# Longde1.net
KiCad netlist of a schematic drawn in Altium Designer
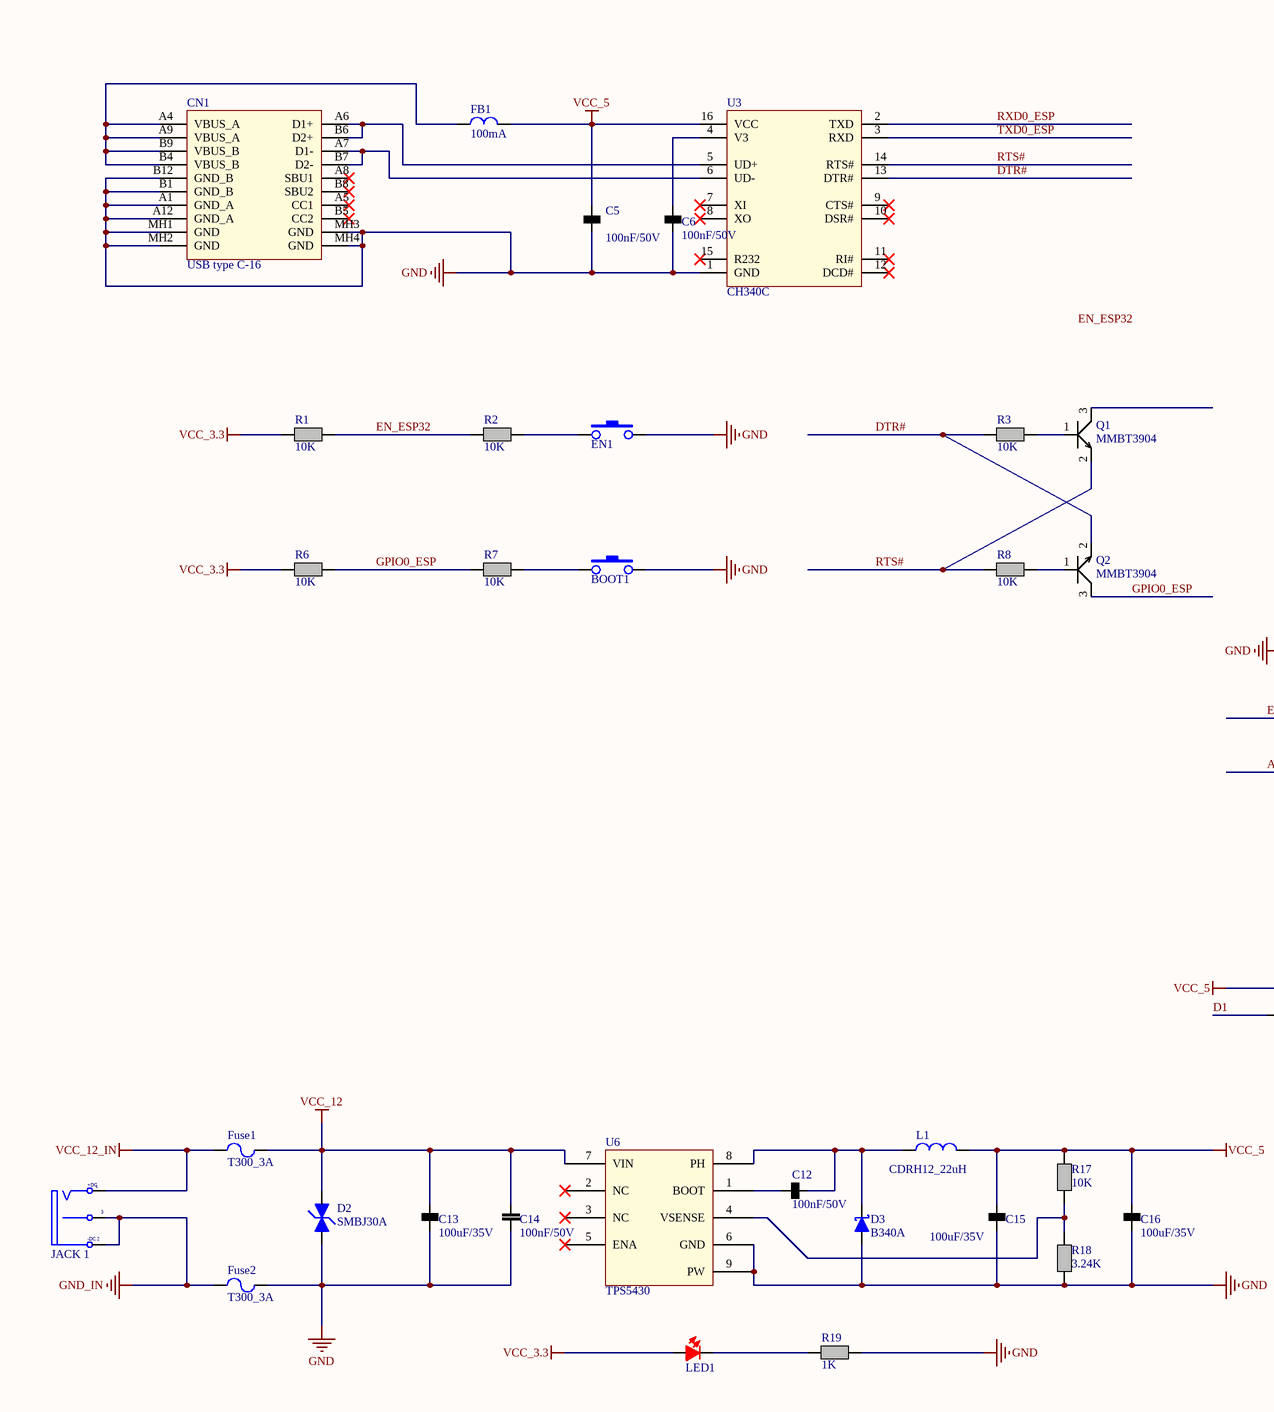
[diagram p0: Longde1.SchDoc, left]
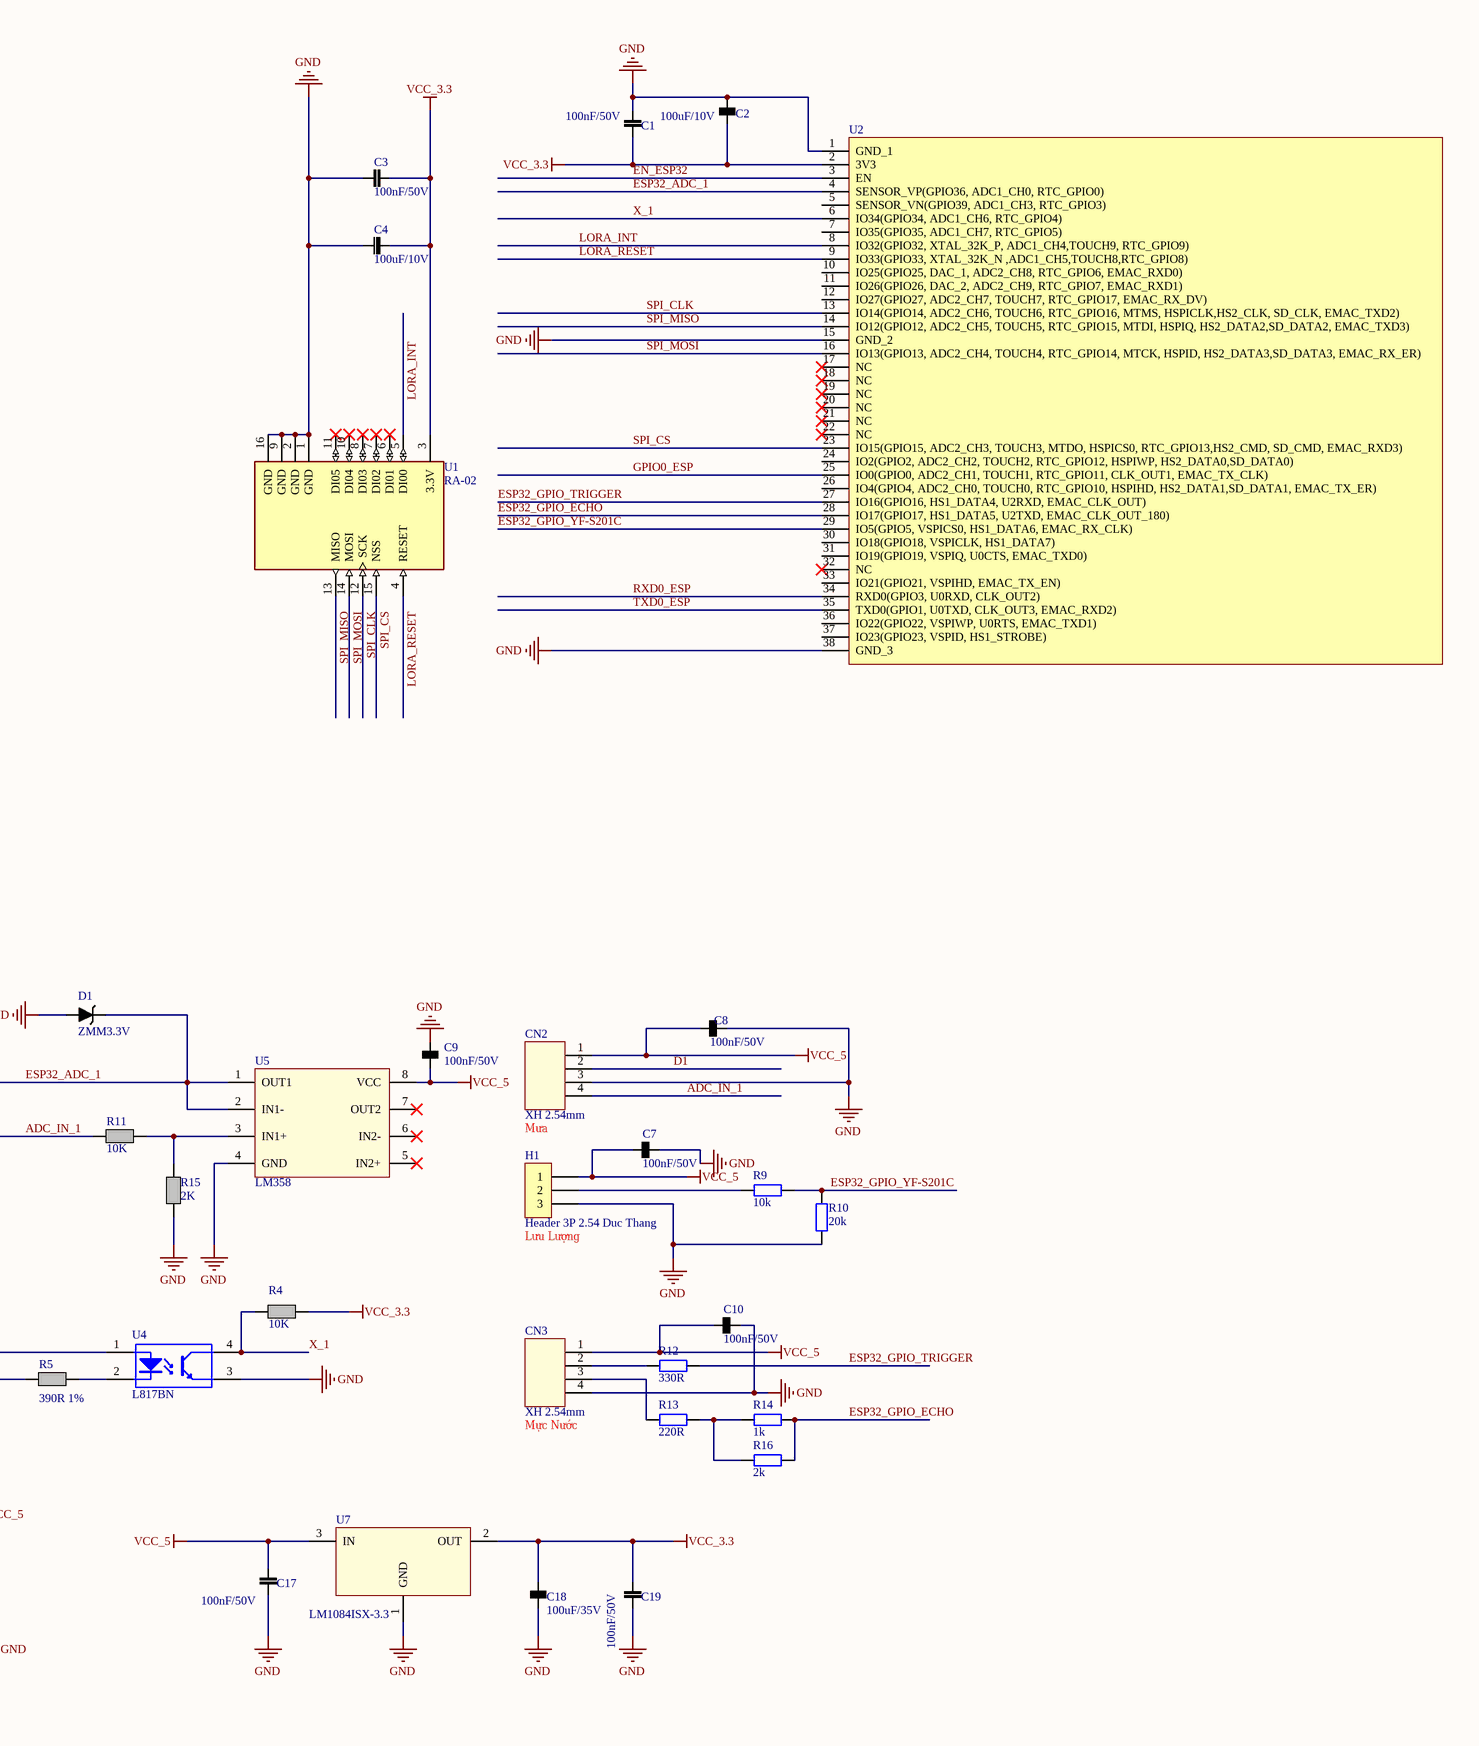
[diagram p1: Longde1.SchDoc, right]

(export (version "E")
  (design (tool "Eeschema 10.0.6"))
  (components
    (comp (ref "BOOT1")
      (value "SW_2pin_SMD")
      (footprint "SW2-SMD**")
      (libsource (lib "Milky_Way") (part "SW_2pin_SMD"))
    )
    (comp (ref "C1")
      (value "100nF/50V")
      (footprint "CAP-0805**")
      (description "2Pin-SMD-0805 ,Ceramic X7R")
      (libsource (lib "Milky_Way") (part "Cap-100nF/50V_0805"))
    )
    (comp (ref "C2")
      (value "100uF/10V")
      (footprint "CAP-TANTA-3528**")
      (description "Cap-Tantalum  SMD3528 3.5mm x 2.8mm")
      (libsource (lib "") (part "Cap-Tanta_100uF/10V 3528_1"))
    )
    (comp (ref "C3")
      (value "100nF/50V")
      (footprint "CAP-0805**")
      (description "2Pin-SMD-0805 ,Ceramic X7R")
      (libsource (lib "Milky_Way") (part "Cap-100nF/50V_0805"))
    )
    (comp (ref "C4")
      (value "100uF/10V")
      (footprint "CAP-TANTA-3528**")
      (description "Cap-Tantalum  SMD3528 3.5mm x 2.8mm")
      (libsource (lib "Milky_Way") (part "Cap-Tanta_100uF/10V 3528"))
    )
    (comp (ref "C5")
      (value "100nF/50V")
      (footprint "CAP-0805**")
      (description "2Pin-SMD-0805 ,Ceramic X7R")
      (libsource (lib "Milky_Way") (part "Cap-100nF/50V_0805"))
    )
    (comp (ref "C6")
      (value "100nF/50V")
      (footprint "CAP-0805**")
      (description "2Pin-SMD-0805 ,Ceramic X7R")
      (libsource (lib "Milky_Way") (part "Cap-100nF/50V_0805"))
    )
    (comp (ref "C7")
      (value "100nF/50V")
      (footprint "CAP-0805**")
      (description "2Pin-SMD-0805 ,Ceramic X7R")
      (libsource (lib "Milky_Way") (part "Cap-100nF/50V_0805"))
    )
    (comp (ref "C8")
      (value "100nF/50V")
      (footprint "CAP-0805**")
      (description "2Pin-SMD-0805 ,Ceramic X7R")
      (libsource (lib "Milky_Way") (part "Cap-100nF/50V_0805"))
    )
    (comp (ref "C9")
      (value "100nF/50V")
      (footprint "CAP-0805**")
      (description "2Pin-SMD-0805 ,Ceramic X7R")
      (libsource (lib "Milky_Way") (part "Cap-100nF/50V_0805"))
    )
    (comp (ref "C10")
      (value "100nF/50V")
      (footprint "CAP-0805**")
      (description "2Pin-SMD-0805 ,Ceramic X7R")
      (libsource (lib "Milky_Way") (part "Cap-100nF/50V_0805"))
    )
    (comp (ref "C12")
      (value "100nF/50V")
      (footprint "CAP-0805**")
      (description "2Pin-SMD-0805 ,Ceramic X7R")
      (libsource (lib "Milky_Way") (part "Cap-100nF/50V_0805"))
    )
    (comp (ref "C13")
      (value "100uF/35V")
      (footprint "CAP-AL- Size D8_6.3×7.7 mm**")
      (description "Cap-Al-Size D8_6.3×7.7 mm")
      (libsource (lib "Milky_Way") (part "Cap-Al_100uF/35V"))
    )
    (comp (ref "C14")
      (value "100nF/50V")
      (footprint "CAP-0805**")
      (description "2Pin-SMD-0805 ,Ceramic X7R")
      (libsource (lib "Milky_Way") (part "Cap-100nF/50V_0805"))
    )
    (comp (ref "C15")
      (value "100uF/35V")
      (footprint "CAP-AL- Size D8_6.3×7.7 mm**")
      (description "Cap-Al-Size D8_6.3×7.7 mm")
      (libsource (lib "Milky_Way") (part "Cap-Al_100uF/35V"))
    )
    (comp (ref "C16")
      (value "100uF/35V")
      (footprint "CAP-AL- Size D8_6.3×7.7 mm**")
      (description "Cap-Al-Size D8_6.3×7.7 mm")
      (libsource (lib "Milky_Way") (part "Cap-Al_100uF/35V"))
    )
    (comp (ref "C17")
      (value "100nF/50V")
      (footprint "CAP-0805**")
      (description "2Pin-SMD-0805 ,Ceramic X7R")
      (libsource (lib "Milky_Way") (part "Cap-100nF/50V_0805"))
    )
    (comp (ref "C18")
      (value "100uF/35V")
      (footprint "CAP-AL- Size D8_6.3×7.7 mm**")
      (description "Cap-Al-Size D8_6.3×7.7 mm")
      (libsource (lib "Milky_Way") (part "Cap-Al_100uF/35V"))
    )
    (comp (ref "C19")
      (value "100nF/50V")
      (footprint "CAP-0805**")
      (description "2Pin-SMD-0805 ,Ceramic X7R")
      (libsource (lib "Milky_Way") (part "Cap-100nF/50V_0805"))
    )
    (comp (ref "CN1")
      (value "USB type C-16")
      (footprint "USB TYPE C-16**")
      (fields (field (name "MF") "Valcon") (field (name "MP") "CSP-USC16-TR"))
      (libsource (lib "Milky_Way") (part "USB type C-16"))
    )
    (comp (ref "CN2")
      (value "XH 2.54mm")
      (footprint "HER_XH2.54MM _4PIN_STRAGHT**")
      (description "HER_4_XH 2.54mm")
      (libsource (lib "Milky_Way") (part "HER_4_XH 2.54mm"))
    )
    (comp (ref "CN3")
      (value "XH 2.54mm")
      (footprint "HER_XH2.54MM _4PIN_STRAGHT**")
      (description "HER_4_XH 2.54mm")
      (libsource (lib "Milky_Way") (part "HER_4_XH 2.54mm"))
    )
    (comp (ref "D1")
      (value "ZMM3.3V")
      (footprint "DIO_SOD-80C**")
      (description "DZener_ZMM3.3V,SOD-80C")
      (libsource (lib "Milky_Way") (part "DZener_ZMM3.3V"))
    )
    (comp (ref "D2")
      (value "SMBJ30A")
      (footprint "DO-214AA**")
      (description "DO-214AA**")
      (libsource (lib "Milky_Way") (part "D-TVS_SMBJ30A"))
    )
    (comp (ref "D3")
      (value "B340A")
      (footprint "DO-214AC**")
      (description "DO_214AC")
      (fields (field (name "PUBLISHER") "Altium Limited"))
      (libsource (lib "Milky_Way") (part "DSchottky_B340A"))
    )
    (comp (ref "EN1")
      (value "SW_2pin_SMD")
      (footprint "SW2-SMD**")
      (libsource (lib "Milky_Way") (part "SW_2pin_SMD"))
    )
    (comp (ref "FB1")
      (value "100mA")
      (footprint "FB 0805**")
      (description "FB0805/600R/0805")
      (fields (field (name "PUBLISHER") "Altium Limited"))
      (libsource (lib "Milky_Way") (part "FB0805/600R_0805"))
    )
    (comp (ref "Fuse1")
      (value "T300_3A")
      (footprint "FUSE-1812**")
      (description "SMD 1812")
      (libsource (lib "Milky_Way") (part "FUSE 3A _1812"))
    )
    (comp (ref "Fuse2")
      (value "T300_3A")
      (footprint "FUSE-1812**")
      (description "SMD 1812")
      (libsource (lib "Milky_Way") (part "FUSE 3A _1812"))
    )
    (comp (ref "H1")
      (value "Header 3P 2.54 Duc Thang")
      (footprint "XH2.54M-3")
      (description "Cắm")
      (libsource (lib "Altium_Lib_by_KhueNguyenCreator") (part "Header 3P 2.54 Duc Thang"))
    )
    (comp (ref "JACK 1")
      (value "DC3501")
      (footprint "DC_005**")
      (description "Jack DC3.5x1.3MM DC3501")
      (libsource (lib "Milky_Way") (part "Jack  DC3501"))
    )
    (comp (ref "L1")
      (value "CDRH12_22uH")
      (footprint "IND_CDRH12_12x12x7MM**")
      (description "CDRH12_12x12x7MM**")
      (fields
        (field (name "MANUFACTURER") "Generic Components")
        (field (name "PUBLISHER") "Altium Hobart Technology Centre")
      )
      (libsource (lib "Milky_Way") (part "IN_CDRH12_22uH"))
    )
    (comp (ref "LED1")
      (value "LedRed")
      (footprint "LED-0805-Red**")
      (description "2Pin-SMD")
      (libsource (lib "Milky_Way") (part "LedRed"))
    )
    (comp (ref "Q1")
      (value "MMBT3904")
      (footprint "SOT23-3 **")
      (description "3PIN-SOT23,MMBT3904")
      (libsource (lib "Milky_Way") (part "TRA-N_MMBT3904"))
    )
    (comp (ref "Q2")
      (value "MMBT3904")
      (footprint "SOT23-3 **")
      (description "3PIN-SOT23,MMBT3904")
      (libsource (lib "Milky_Way") (part "TRA-N_MMBT3904"))
    )
    (comp (ref "R1")
      (value "10K")
      (footprint "Res-0805**")
      (description "Res-10K 0805 SMD")
      (libsource (lib "Milky_Way") (part "Res-10K 0805 SMD"))
    )
    (comp (ref "R2")
      (value "10K")
      (footprint "Res-0805**")
      (description "Res-10K 0805 SMD")
      (libsource (lib "Milky_Way") (part "Res-10K 0805 SMD"))
    )
    (comp (ref "R3")
      (value "10K")
      (footprint "Res-0805**")
      (description "Res-10K 0805 SMD")
      (libsource (lib "Milky_Way") (part "Res-10K 0805 SMD"))
    )
    (comp (ref "R4")
      (value "10K")
      (footprint "Res-0805**")
      (description "Res-10K 0805 SMD")
      (libsource (lib "Milky_Way") (part "Res-10K 0805 SMD"))
    )
    (comp (ref "R5")
      (value "390R 1%")
      (footprint "Res-0805**")
      (libsource (lib "Milky_Way") (part "Res-390R 1% 0805 SMD"))
    )
    (comp (ref "R6")
      (value "10K")
      (footprint "Res-0805**")
      (description "Res-10K 0805 SMD")
      (libsource (lib "Milky_Way") (part "Res-10K 0805 SMD"))
    )
    (comp (ref "R7")
      (value "10K")
      (footprint "Res-0805**")
      (description "Res-10K 0805 SMD")
      (libsource (lib "Milky_Way") (part "Res-10K 0805 SMD"))
    )
    (comp (ref "R8")
      (value "10K")
      (footprint "Res-0805**")
      (description "Res-10K 0805 SMD")
      (libsource (lib "Milky_Way") (part "Res-10K 0805 SMD"))
    )
    (comp (ref "R9")
      (value "10k")
      (footprint "tro smd 0805")
      (description "Dán")
      (libsource (lib "ThuvienTHoi") (part "Tro 0805 1% 10k"))
    )
    (comp (ref "R10")
      (value "20k")
      (footprint "tro smd 0805")
      (description "Dán")
      (libsource (lib "ThuvienTHoi") (part "Tro 0805 5% 20k"))
    )
    (comp (ref "R11")
      (value "10K")
      (footprint "Res-0805**")
      (description "Res-10K 0805 SMD")
      (libsource (lib "Milky_Way") (part "Res-10K 0805 SMD"))
    )
    (comp (ref "R12")
      (value "330R")
      (footprint "Tro SMD 0805")
      (description "Dán")
      (libsource (lib "ThuVienHA") (part "Tro 0805 5% 330R"))
    )
    (comp (ref "R13")
      (value "220R")
      (footprint "tro smd 0805")
      (description "Dán")
      (libsource (lib "Altium_Lib_by_KhueNguyenCreator") (part "Tro 0805 5% 220R"))
    )
    (comp (ref "R14")
      (value "1k")
      (footprint "tro smd 0805")
      (description "Dán")
      (libsource (lib "Altium_Lib_by_KhueNguyenCreator") (part "Tro 0805 1% 1k"))
    )
    (comp (ref "R15")
      (value "2K")
      (footprint "Res-0805**")
      (description "Res-2KK 0805 SMD")
      (libsource (lib "Milky_Way") (part "Res-2K 0805 SMD"))
    )
    (comp (ref "R16")
      (value "2k")
      (footprint "Tro SMD 0805")
      (description "Dán")
      (libsource (lib "Altium_Lib_by_KhueNguyenCreator") (part "Tro 0805 5% 2k"))
    )
    (comp (ref "R17")
      (value "10K")
      (footprint "Res-0805**")
      (description "Res-10K 0805 SMD")
      (libsource (lib "Milky_Way") (part "Res-10K 0805 SMD"))
    )
    (comp (ref "R18")
      (value "3.24K")
      (footprint "Res-0805**")
      (description "Res-3.24K 0805 SMD")
      (libsource (lib "Milky_Way") (part "Res-3.24K 0805 SMD"))
    )
    (comp (ref "R19")
      (value "1K")
      (footprint "Res-0805**")
      (description "Res-1K 0805 SMD")
      (libsource (lib "Milky_Way") (part "Res-1K 0805 SMD"))
    )
    (comp (ref "U1")
      (value "RA-02")
      (footprint "RA-02")
      (fields (field (name "MF") "Ai-Thinker"))
      (libsource (lib "RA-02") (part "RA-02"))
    )
    (comp (ref "U2")
      (value "~")
      (footprint "ESP32WROOM32E8MB")
      (description "Integrated Circuit")
      (fields
        (field (name "MANUFACTURER_PART_NUMBER") "ESP32-WROOM-32E (8MB)")
        (field (name "MOUSER PART NUMBER") "356-ESP32WRM32E164PH")
      )
      (libsource (lib "ThuVienDoAn") (part "ESP32-WROOM-32E__8MB_"))
    )
    (comp (ref "U3")
      (value "CH340C")
      (footprint "SOIC-16**")
      (description "16Pin-SOIC")
      (libsource (lib "Milky_Way") (part "CH340C"))
    )
    (comp (ref "U4")
      (value "L817BN")
      (footprint "SOP-4**")
      (description "L817BN SOP4")
      (libsource (lib "Milky_Way") (part "OPTO_L817BN"))
    )
    (comp (ref "U5")
      (value "LM358")
      (footprint "SOIC8**")
      (description "SOIC8")
      (libsource (lib "Milky_Way") (part "LM358"))
    )
    (comp (ref "U6")
      (value "TPS5430")
      (footprint "SOIC8-PAD**")
      (description "SOIC8 pad-Height 1.7mm")
      (libsource (lib "Milky_Way") (part "TPS5430"))
    )
    (comp (ref "U7")
      (value "LM1084ISX-3.3")
      (footprint "TO-263/D2PAK")
      (description "TO263-3")
      (libsource (lib "Milky_Way") (part "LM1084ISX-3.3"))
    )
  )
  (nets
    (net (code "1") (name "/ADC_IN_1") (class "Default")
      (node (ref "CN2") (pin "4") (pinfunction "4_4") (pintype "passive"))
      (node (ref "R11") (pin "2") (pinfunction "2_2") (pintype "passive"))
    )
    (net (code "2") (name "/D1") (class "Default")
      (node (ref "CN2") (pin "2") (pinfunction "2_2") (pintype "passive"))
      (node (ref "R5") (pin "1") (pinfunction "1_1") (pintype "passive"))
    )
    (net (code "3") (name "/DTR#") (class "Default")
      (node (ref "Q2") (pin "2") (pinfunction "2_2") (pintype "passive"))
      (node (ref "R3") (pin "2") (pinfunction "2_2") (pintype "passive"))
      (node (ref "U3") (pin "13") (pinfunction "DTR#_13") (pintype "passive"))
    )
    (net (code "4") (name "/EN_ESP32") (class "Default")
      (node (ref "R1") (pin "1") (pinfunction "1_1") (pintype "passive"))
      (node (ref "R2") (pin "2") (pinfunction "2_2") (pintype "passive"))
      (node (ref "U2") (pin "3") (pinfunction "EN_3") (pintype "passive"))
    )
    (net (code "5") (name "/ESP32_ADC_1") (class "Default")
      (node (ref "D1") (pin "2") (pinfunction "K_2") (pintype "passive"))
      (node (ref "U2") (pin "4") (pinfunction "SENSOR_VP(GPIO36,_ADC1_CH0,_RTC_GPIO0)_4") (pintype "passive"))
      (node (ref "U5") (pin "1") (pinfunction "OUT1_1") (pintype "passive"))
      (node (ref "U5") (pin "2") (pinfunction "IN1-_2") (pintype "passive"))
    )
    (net (code "6") (name "/ESP32_GPIO_ECHO") (class "Default")
      (node (ref "R14") (pin "2") (pinfunction "2_2") (pintype "passive"))
      (node (ref "R16") (pin "2") (pinfunction "2_2") (pintype "passive"))
      (node (ref "U2") (pin "28") (pinfunction "IO17(GPIO17,_HS1_DATA5,_U2TXD,_EMAC_CLK_OUT_180)_28") (pintype "passive"))
    )
    (net (code "7") (name "/ESP32_GPIO_TRIGGER") (class "Default")
      (node (ref "R12") (pin "2") (pinfunction "2_2") (pintype "passive"))
      (node (ref "U2") (pin "27") (pinfunction "IO16(GPIO16,_HS1_DATA4,_U2RXD,_EMAC_CLK_OUT)_27") (pintype "passive"))
    )
    (net (code "8") (name "/ESP32_GPIO_YF-S201C") (class "Default")
      (node (ref "R10") (pin "2") (pinfunction "2_2") (pintype "passive"))
      (node (ref "R9") (pin "2") (pinfunction "2_2") (pintype "passive"))
      (node (ref "U2") (pin "29") (pinfunction "IO5(GPIO5,_VSPICS0,_HS1_DATA6,_EMAC_RX_CLK)_29") (pintype "passive"))
    )
    (net (code "9") (name "/GPIO0_ESP") (class "Default")
      (node (ref "Q2") (pin "3") (pinfunction "3_3") (pintype "passive"))
      (node (ref "R6") (pin "1") (pinfunction "1_1") (pintype "passive"))
      (node (ref "R7") (pin "2") (pinfunction "2_2") (pintype "passive"))
      (node (ref "U2") (pin "25") (pinfunction "IO0(GPIO0,_ADC2_CH1,_TOUCH1,_RTC_GPIO11,_CLK_OUT1,_EMAC_TX_CLK)_25") (pintype "passive"))
    )
    (net (code "10") (name "/LORA_INT") (class "Default")
      (node (ref "U1") (pin "5") (pinfunction "DI00_5") (pintype "bidirectional"))
      (node (ref "U2") (pin "8") (pinfunction "IO32(GPIO32,_XTAL_32K_P,_ADC1_CH4,TOUCH9,_RTC_GPIO9)_8") (pintype "passive"))
    )
    (net (code "11") (name "/LORA_RESET") (class "Default")
      (node (ref "U1") (pin "4") (pinfunction "RESET_4") (pintype "input"))
      (node (ref "U2") (pin "9") (pinfunction "IO33(GPIO33,_XTAL_32K_N_,ADC1_CH5,TOUCH8,RTC_GPIO8)_9") (pintype "passive"))
    )
    (net (code "12") (name "/RTS#") (class "Default")
      (node (ref "Q1") (pin "2") (pinfunction "2_2") (pintype "passive"))
      (node (ref "R8") (pin "2") (pinfunction "2_2") (pintype "passive"))
      (node (ref "U3") (pin "14") (pinfunction "RTS#_14") (pintype "passive"))
    )
    (net (code "13") (name "/RXD0_ESP") (class "Default")
      (node (ref "U2") (pin "34") (pinfunction "RXD0(GPIO3,_U0RXD,_CLK_OUT2)_34") (pintype "passive"))
      (node (ref "U3") (pin "2") (pinfunction "TXD_2") (pintype "passive"))
    )
    (net (code "14") (name "/SPI_CLK") (class "Default")
      (node (ref "U1") (pin "12") (pinfunction "SCK_12") (pintype "input"))
      (node (ref "U2") (pin "13") (pinfunction "IO14(GPIO14,_ADC2_CH6,_TOUCH6,_RTC_GPIO16,_MTMS,_HSPICLK,HS2_CLK,_SD_CLK,_EMAC_TXD2)_13") (pintype "passive"))
    )
    (net (code "15") (name "/SPI_CS") (class "Default")
      (node (ref "U1") (pin "15") (pinfunction "NSS_15") (pintype "input"))
      (node (ref "U2") (pin "23") (pinfunction "IO15(GPIO15,_ADC2_CH3,_TOUCH3,_MTDO,_HSPICS0,_RTC_GPIO13,HS2_CMD,_SD_CMD,_EMAC_RXD3)_23") (pintype "passive"))
    )
    (net (code "16") (name "/SPI_MISO") (class "Default")
      (node (ref "U1") (pin "13") (pinfunction "MISO_13") (pintype "output"))
      (node (ref "U2") (pin "14") (pinfunction "IO12(GPIO12,_ADC2_CH5,_TOUCH5,_RTC_GPIO15,_MTDI,_HSPIQ,_HS2_DATA2,SD_DATA2,_EMAC_TXD3)_14") (pintype "passive"))
    )
    (net (code "17") (name "/SPI_MOSI") (class "Default")
      (node (ref "U1") (pin "14") (pinfunction "MOSI_14") (pintype "input"))
      (node (ref "U2") (pin "16") (pinfunction "IO13(GPIO13,_ADC2_CH4,_TOUCH4,_RTC_GPIO14,_MTCK,_HSPID,_HS2_DATA3,SD_DATA3,_EMAC_RX_ER)_16") (pintype "passive"))
    )
    (net (code "18") (name "/TXD0_ESP") (class "Default")
      (node (ref "U2") (pin "35") (pinfunction "TXD0(GPIO1,_U0TXD,_CLK_OUT3,_EMAC_RXD2)_35") (pintype "passive"))
      (node (ref "U3") (pin "3") (pinfunction "RXD_3") (pintype "passive"))
    )
    (net (code "19") (name "/X_1") (class "Default")
      (node (ref "R4") (pin "2") (pinfunction "2_2") (pintype "passive"))
      (node (ref "U2") (pin "6") (pinfunction "IO34(GPIO34,_ADC1_CH6,_RTC_GPIO4)_6") (pintype "passive"))
      (node (ref "U4") (pin "4") (pinfunction "4_4") (pintype "passive"))
    )
    (net (code "20") (name "GND") (class "Default")
      (node (ref "BOOT1") (pin "2") (pinfunction "2_2") (pintype "passive"))
      (node (ref "C1") (pin "2") (pinfunction "2_2") (pintype "passive"))
      (node (ref "C10") (pin "1") (pinfunction "1_1") (pintype "passive"))
      (node (ref "C13") (pin "2") (pinfunction "-_2") (pintype "passive"))
      (node (ref "C14") (pin "1") (pinfunction "1_1") (pintype "passive"))
      (node (ref "C15") (pin "2") (pinfunction "-_2") (pintype "passive"))
      (node (ref "C16") (pin "2") (pinfunction "-_2") (pintype "passive"))
      (node (ref "C17") (pin "1") (pinfunction "1_1") (pintype "passive"))
      (node (ref "C18") (pin "2") (pinfunction "-_2") (pintype "passive"))
      (node (ref "C19") (pin "1") (pinfunction "1_1") (pintype "passive"))
      (node (ref "C2") (pin "2") (pinfunction "-_2") (pintype "passive"))
      (node (ref "C3") (pin "1") (pinfunction "1_1") (pintype "passive"))
      (node (ref "C4") (pin "2") (pinfunction "-_2") (pintype "passive"))
      (node (ref "C5") (pin "2") (pinfunction "2_2") (pintype "passive"))
      (node (ref "C6") (pin "2") (pinfunction "2_2") (pintype "passive"))
      (node (ref "C7") (pin "1") (pinfunction "1_1") (pintype "passive"))
      (node (ref "C8") (pin "1") (pinfunction "1_1") (pintype "passive"))
      (node (ref "C9") (pin "2") (pinfunction "2_2") (pintype "passive"))
      (node (ref "CN1") (pin "A1") (pinfunction "GND_A_A1") (pintype "power_in"))
      (node (ref "CN1") (pin "A12") (pinfunction "GND_A_A12") (pintype "power_in"))
      (node (ref "CN1") (pin "B1") (pinfunction "GND_B_B1") (pintype "power_in"))
      (node (ref "CN1") (pin "B12") (pinfunction "GND_B_B12") (pintype "power_in"))
      (node (ref "CN1") (pin "MH1") (pinfunction "GND_MH1") (pintype "power_in"))
      (node (ref "CN1") (pin "MH2") (pinfunction "GND_MH2") (pintype "power_in"))
      (node (ref "CN1") (pin "MH3") (pinfunction "GND_MH3") (pintype "power_in"))
      (node (ref "CN1") (pin "MH4") (pinfunction "GND_MH4") (pintype "power_in"))
      (node (ref "CN2") (pin "3") (pinfunction "3_3") (pintype "passive"))
      (node (ref "CN3") (pin "4") (pinfunction "4_4") (pintype "passive"))
      (node (ref "D1") (pin "1") (pinfunction "A_1") (pintype "passive"))
      (node (ref "D2") (pin "1") (pinfunction "A_1") (pintype "passive"))
      (node (ref "D3") (pin "1") (pinfunction "A_1") (pintype "passive"))
      (node (ref "EN1") (pin "2") (pinfunction "2_2") (pintype "passive"))
      (node (ref "Fuse2") (pin "2") (pinfunction "2_2") (pintype "passive"))
      (node (ref "H1") (pin "3") (pinfunction "3_3") (pintype "passive"))
      (node (ref "R10") (pin "1") (pinfunction "1_1") (pintype "passive"))
      (node (ref "R15") (pin "1") (pinfunction "1_1") (pintype "passive"))
      (node (ref "R18") (pin "1") (pinfunction "1_1") (pintype "passive"))
      (node (ref "R19") (pin "1") (pinfunction "1_1") (pintype "passive"))
      (node (ref "U1") (pin "1") (pinfunction "GND_1") (pintype "power_in"))
      (node (ref "U1") (pin "16") (pinfunction "GND_16") (pintype "power_in"))
      (node (ref "U1") (pin "2") (pinfunction "GND_2") (pintype "power_in"))
      (node (ref "U1") (pin "9") (pinfunction "GND_9") (pintype "power_in"))
      (node (ref "U2") (pin "1") (pinfunction "GND_1_1") (pintype "passive"))
      (node (ref "U2") (pin "15") (pinfunction "GND_2_15") (pintype "passive"))
      (node (ref "U2") (pin "38") (pinfunction "GND_3_38") (pintype "passive"))
      (node (ref "U3") (pin "1") (pinfunction "GND_1") (pintype "passive"))
      (node (ref "U4") (pin "3") (pinfunction "3_3") (pintype "passive"))
      (node (ref "U5") (pin "4") (pinfunction "GND_4") (pintype "passive"))
      (node (ref "U6") (pin "6") (pinfunction "GND_6") (pintype "passive"))
      (node (ref "U6") (pin "9") (pinfunction "PW_9") (pintype "passive"))
      (node (ref "U7") (pin "1") (pinfunction "GND_1") (pintype "passive"))
    )
    (net (code "21") (name "GND_IN") (class "Default")
      (node (ref "Fuse2") (pin "1") (pinfunction "1_1") (pintype "passive"))
      (node (ref "JACK 1") (pin "2") (pinfunction "TN_2") (pintype "passive"))
      (node (ref "JACK 1") (pin "3") (pinfunction "S_3") (pintype "power_in"))
    )
    (net (code "22") (name "Net-(BOOT1-Pad1)") (class "Default")
      (node (ref "BOOT1") (pin "1") (pinfunction "1_1") (pintype "passive"))
      (node (ref "R7") (pin "1") (pinfunction "1_1") (pintype "passive"))
    )
    (net (code "23") (name "Net-(CN1-D1+)") (class "Default")
      (node (ref "CN1") (pin "A6") (pinfunction "D1+_A6") (pintype "passive"))
      (node (ref "CN1") (pin "B6") (pinfunction "D2+_B6") (pintype "passive"))
      (node (ref "U3") (pin "5") (pinfunction "UD+_5") (pintype "passive"))
    )
    (net (code "24") (name "Net-(CN1-D1-)") (class "Default")
      (node (ref "CN1") (pin "A7") (pinfunction "D1-_A7") (pintype "passive"))
      (node (ref "CN1") (pin "B7") (pinfunction "D2-_B7") (pintype "passive"))
      (node (ref "U3") (pin "6") (pinfunction "UD-_6") (pintype "passive"))
    )
    (net (code "25") (name "Net-(CN1-VBUS_A-PadA4)") (class "Default")
      (node (ref "CN1") (pin "A4") (pinfunction "VBUS_A_A4") (pintype "power_in"))
      (node (ref "CN1") (pin "A9") (pinfunction "VBUS_A_A9") (pintype "power_in"))
      (node (ref "CN1") (pin "B4") (pinfunction "VBUS_B_B4") (pintype "power_in"))
      (node (ref "CN1") (pin "B9") (pinfunction "VBUS_B_B9") (pintype "power_in"))
      (node (ref "FB1") (pin "1") (pinfunction "1_1") (pintype "passive"))
    )
    (net (code "26") (name "Net-(CN3-Pad2)") (class "Default")
      (node (ref "CN3") (pin "2") (pinfunction "2_2") (pintype "passive"))
      (node (ref "R12") (pin "1") (pinfunction "1_1") (pintype "passive"))
    )
    (net (code "27") (name "Net-(CN3-Pad3)") (class "Default")
      (node (ref "CN3") (pin "3") (pinfunction "3_3") (pintype "passive"))
      (node (ref "R13") (pin "1") (pinfunction "1_1") (pintype "passive"))
    )
    (net (code "28") (name "Net-(D3-K)") (class "Default")
      (node (ref "C12") (pin "2") (pinfunction "2_2") (pintype "passive"))
      (node (ref "D3") (pin "2") (pinfunction "K_2") (pintype "passive"))
      (node (ref "L1") (pin "1") (pinfunction "1_1") (pintype "passive"))
      (node (ref "U6") (pin "8") (pinfunction "PH_8") (pintype "passive"))
    )
    (net (code "29") (name "Net-(EN1-Pad1)") (class "Default")
      (node (ref "EN1") (pin "1") (pinfunction "1_1") (pintype "passive"))
      (node (ref "R2") (pin "1") (pinfunction "1_1") (pintype "passive"))
    )
    (net (code "30") (name "Net-(H1-Pad2)") (class "Default")
      (node (ref "H1") (pin "2") (pinfunction "2_2") (pintype "passive"))
      (node (ref "R9") (pin "1") (pinfunction "1_1") (pintype "passive"))
    )
    (net (code "31") (name "Net-(LED1-K)") (class "Default")
      (node (ref "LED1") (pin "2") (pinfunction "K_2") (pintype "passive"))
      (node (ref "R19") (pin "2") (pinfunction "2_2") (pintype "passive"))
    )
    (net (code "32") (name "Net-(Q1-Pad1)") (class "Default")
      (node (ref "Q1") (pin "1") (pinfunction "1_1") (pintype "passive"))
      (node (ref "R3") (pin "1") (pinfunction "1_1") (pintype "passive"))
    )
    (net (code "33") (name "Net-(Q2-Pad1)") (class "Default")
      (node (ref "Q2") (pin "1") (pinfunction "1_1") (pintype "passive"))
      (node (ref "R8") (pin "1") (pinfunction "1_1") (pintype "passive"))
    )
    (net (code "34") (name "Net-(R5-Pad2)") (class "Default")
      (node (ref "R5") (pin "2") (pinfunction "2_2") (pintype "passive"))
      (node (ref "U4") (pin "2") (pinfunction "2_2") (pintype "passive"))
    )
    (net (code "35") (name "Net-(R13-Pad2)") (class "Default")
      (node (ref "R13") (pin "2") (pinfunction "2_2") (pintype "passive"))
      (node (ref "R14") (pin "1") (pinfunction "1_1") (pintype "passive"))
      (node (ref "R16") (pin "1") (pinfunction "1_1") (pintype "passive"))
    )
    (net (code "36") (name "Net-(U3-V3)") (class "Default")
      (node (ref "C6") (pin "1") (pinfunction "1_1") (pintype "passive"))
      (node (ref "U3") (pin "4") (pinfunction "V3_4") (pintype "passive"))
    )
    (net (code "37") (name "Net-(U5-IN1+)") (class "Default")
      (node (ref "R11") (pin "1") (pinfunction "1_1") (pintype "passive"))
      (node (ref "R15") (pin "2") (pinfunction "2_2") (pintype "passive"))
      (node (ref "U5") (pin "3") (pinfunction "IN1+_3") (pintype "passive"))
    )
    (net (code "38") (name "Net-(U6-BOOT)") (class "Default")
      (node (ref "C12") (pin "1") (pinfunction "1_1") (pintype "passive"))
      (node (ref "U6") (pin "1") (pinfunction "BOOT_1") (pintype "passive"))
    )
    (net (code "39") (name "Net-(U6-VSENSE)") (class "Default")
      (node (ref "R17") (pin "1") (pinfunction "1_1") (pintype "passive"))
      (node (ref "R18") (pin "2") (pinfunction "2_2") (pintype "passive"))
      (node (ref "U6") (pin "4") (pinfunction "VSENSE_4") (pintype "passive"))
    )
    (net (code "40") (name "VCC_3.3") (class "Default")
      (node (ref "C1") (pin "1") (pinfunction "1_1") (pintype "passive"))
      (node (ref "C18") (pin "1") (pinfunction "+_1") (pintype "passive"))
      (node (ref "C19") (pin "2") (pinfunction "2_2") (pintype "passive"))
      (node (ref "C2") (pin "1") (pinfunction "+_1") (pintype "passive"))
      (node (ref "C3") (pin "2") (pinfunction "2_2") (pintype "passive"))
      (node (ref "C4") (pin "1") (pinfunction "+_1") (pintype "passive"))
      (node (ref "LED1") (pin "1") (pinfunction "A_1") (pintype "passive"))
      (node (ref "R1") (pin "2") (pinfunction "2_2") (pintype "passive"))
      (node (ref "R4") (pin "1") (pinfunction "1_1") (pintype "passive"))
      (node (ref "R6") (pin "2") (pinfunction "2_2") (pintype "passive"))
      (node (ref "U1") (pin "3") (pinfunction "3.3V_3") (pintype "power_in"))
      (node (ref "U2") (pin "2") (pinfunction "3V3_2") (pintype "passive"))
      (node (ref "U7") (pin "2") (pinfunction "OUT_2") (pintype "passive"))
    )
    (net (code "41") (name "VCC_5") (class "Default")
      (node (ref "C10") (pin "2") (pinfunction "2_2") (pintype "passive"))
      (node (ref "C15") (pin "1") (pinfunction "+_1") (pintype "passive"))
      (node (ref "C16") (pin "1") (pinfunction "+_1") (pintype "passive"))
      (node (ref "C17") (pin "2") (pinfunction "2_2") (pintype "passive"))
      (node (ref "C5") (pin "1") (pinfunction "1_1") (pintype "passive"))
      (node (ref "C7") (pin "2") (pinfunction "2_2") (pintype "passive"))
      (node (ref "C8") (pin "2") (pinfunction "2_2") (pintype "passive"))
      (node (ref "C9") (pin "1") (pinfunction "1_1") (pintype "passive"))
      (node (ref "CN2") (pin "1") (pinfunction "1_1") (pintype "passive"))
      (node (ref "CN3") (pin "1") (pinfunction "1_1") (pintype "passive"))
      (node (ref "FB1") (pin "2") (pinfunction "2_2") (pintype "passive"))
      (node (ref "H1") (pin "1") (pinfunction "1_1") (pintype "passive"))
      (node (ref "L1") (pin "2") (pinfunction "2_2") (pintype "passive"))
      (node (ref "R17") (pin "2") (pinfunction "2_2") (pintype "passive"))
      (node (ref "U3") (pin "16") (pinfunction "VCC_16") (pintype "passive"))
      (node (ref "U4") (pin "1") (pinfunction "1_1") (pintype "passive"))
      (node (ref "U5") (pin "8") (pinfunction "VCC_8") (pintype "passive"))
      (node (ref "U7") (pin "3") (pinfunction "IN_3") (pintype "passive"))
    )
    (net (code "42") (name "VCC_12") (class "Default")
      (node (ref "C13") (pin "1") (pinfunction "+_1") (pintype "passive"))
      (node (ref "C14") (pin "2") (pinfunction "2_2") (pintype "passive"))
      (node (ref "D2") (pin "2") (pinfunction "A_2") (pintype "passive"))
      (node (ref "Fuse1") (pin "2") (pinfunction "2_2") (pintype "passive"))
      (node (ref "U6") (pin "7") (pinfunction "VIN_7") (pintype "passive"))
    )
    (net (code "43") (name "VCC_12_IN") (class "Default")
      (node (ref "Fuse1") (pin "1") (pinfunction "1_1") (pintype "passive"))
      (node (ref "JACK 1") (pin "1") (pinfunction "T_1") (pintype "passive"))
    )
    (net (code "44") (name "unconnected-(CN1-CC1-PadA5)") (class "Default")
      (node (ref "CN1") (pin "A5") (pinfunction "CC1_A5") (pintype "passive+no_connect"))
    )
    (net (code "45") (name "unconnected-(CN1-CC2-PadB5)") (class "Default")
      (node (ref "CN1") (pin "B5") (pinfunction "CC2_B5") (pintype "passive+no_connect"))
    )
    (net (code "46") (name "unconnected-(CN1-SBU1-PadA8)") (class "Default")
      (node (ref "CN1") (pin "A8") (pinfunction "SBU1_A8") (pintype "passive+no_connect"))
    )
    (net (code "47") (name "unconnected-(CN1-SBU2-PadB8)") (class "Default")
      (node (ref "CN1") (pin "B8") (pinfunction "SBU2_B8") (pintype "passive+no_connect"))
    )
    (net (code "48") (name "unconnected-(Q1-Pad3)") (class "Default")
      (node (ref "Q1") (pin "3") (pinfunction "3_3") (pintype "passive"))
    )
    (net (code "49") (name "unconnected-(U1-DI01-Pad6)") (class "Default")
      (node (ref "U1") (pin "6") (pinfunction "DI01_6") (pintype "bidirectional+no_connect"))
    )
    (net (code "50") (name "unconnected-(U1-DI02-Pad7)") (class "Default")
      (node (ref "U1") (pin "7") (pinfunction "DI02_7") (pintype "bidirectional+no_connect"))
    )
    (net (code "51") (name "unconnected-(U1-DI03-Pad8)") (class "Default")
      (node (ref "U1") (pin "8") (pinfunction "DI03_8") (pintype "bidirectional+no_connect"))
    )
    (net (code "52") (name "unconnected-(U1-DI04-Pad10)") (class "Default")
      (node (ref "U1") (pin "10") (pinfunction "DI04_10") (pintype "bidirectional+no_connect"))
    )
    (net (code "53") (name "unconnected-(U1-DI05-Pad11)") (class "Default")
      (node (ref "U1") (pin "11") (pinfunction "DI05_11") (pintype "bidirectional+no_connect"))
    )
    (net (code "54") (name "unconnected-(U2-IO2(GPIO2,_ADC2_CH2,_TOUCH2,_RTC_GPIO12,_HSPIWP,_HS2_DATA0,SD_DATA0)-Pad24)") (class "Default")
      (node (ref "U2") (pin "24") (pinfunction "IO2(GPIO2,_ADC2_CH2,_TOUCH2,_RTC_GPIO12,_HSPIWP,_HS2_DATA0,SD_DATA0)_24") (pintype "passive"))
    )
    (net (code "55") (name "unconnected-(U2-IO4(GPIO4,_ADC2_CH0,_TOUCH0,_RTC_GPIO10,_HSPIHD,_HS2_DATA1,SD_DATA1,_EMAC_TX_ER)-Pad26)") (class "Default")
      (node (ref "U2") (pin "26") (pinfunction "IO4(GPIO4,_ADC2_CH0,_TOUCH0,_RTC_GPIO10,_HSPIHD,_HS2_DATA1,SD_DATA1,_EMAC_TX_ER)_26") (pintype "passive"))
    )
    (net (code "56") (name "unconnected-(U2-IO18(GPIO18,_VSPICLK,_HS1_DATA7)-Pad30)") (class "Default")
      (node (ref "U2") (pin "30") (pinfunction "IO18(GPIO18,_VSPICLK,_HS1_DATA7)_30") (pintype "passive"))
    )
    (net (code "57") (name "unconnected-(U2-IO19(GPIO19,_VSPIQ,_U0CTS,_EMAC_TXD0)-Pad31)") (class "Default")
      (node (ref "U2") (pin "31") (pinfunction "IO19(GPIO19,_VSPIQ,_U0CTS,_EMAC_TXD0)_31") (pintype "passive"))
    )
    (net (code "58") (name "unconnected-(U2-IO21(GPIO21,_VSPIHD,_EMAC_TX_EN)-Pad33)") (class "Default")
      (node (ref "U2") (pin "33") (pinfunction "IO21(GPIO21,_VSPIHD,_EMAC_TX_EN)_33") (pintype "passive"))
    )
    (net (code "59") (name "unconnected-(U2-IO22(GPIO22,_VSPIWP,_U0RTS,_EMAC_TXD1)-Pad36)") (class "Default")
      (node (ref "U2") (pin "36") (pinfunction "IO22(GPIO22,_VSPIWP,_U0RTS,_EMAC_TXD1)_36") (pintype "passive"))
    )
    (net (code "60") (name "unconnected-(U2-IO23(GPIO23,_VSPID,_HS1_STROBE)-Pad37)") (class "Default")
      (node (ref "U2") (pin "37") (pinfunction "IO23(GPIO23,_VSPID,_HS1_STROBE)_37") (pintype "passive"))
    )
    (net (code "61") (name "unconnected-(U2-IO25(GPIO25,_DAC_1,_ADC2_CH8,_RTC_GPIO6,_EMAC_RXD0)-Pad10)") (class "Default")
      (node (ref "U2") (pin "10") (pinfunction "IO25(GPIO25,_DAC_1,_ADC2_CH8,_RTC_GPIO6,_EMAC_RXD0)_10") (pintype "passive"))
    )
    (net (code "62") (name "unconnected-(U2-IO26(GPIO26,_DAC_2,_ADC2_CH9,_RTC_GPIO7,_EMAC_RXD1)-Pad11)") (class "Default")
      (node (ref "U2") (pin "11") (pinfunction "IO26(GPIO26,_DAC_2,_ADC2_CH9,_RTC_GPIO7,_EMAC_RXD1)_11") (pintype "passive"))
    )
    (net (code "63") (name "unconnected-(U2-IO27(GPIO27,_ADC2_CH7,_TOUCH7,_RTC_GPIO17,_EMAC_RX_DV)-Pad12)") (class "Default")
      (node (ref "U2") (pin "12") (pinfunction "IO27(GPIO27,_ADC2_CH7,_TOUCH7,_RTC_GPIO17,_EMAC_RX_DV)_12") (pintype "passive"))
    )
    (net (code "64") (name "unconnected-(U2-IO35(GPIO35,_ADC1_CH7,_RTC_GPIO5)-Pad7)") (class "Default")
      (node (ref "U2") (pin "7") (pinfunction "IO35(GPIO35,_ADC1_CH7,_RTC_GPIO5)_7") (pintype "passive"))
    )
    (net (code "65") (name "unconnected-(U2-NC-Pad17)") (class "Default")
      (node (ref "U2") (pin "17") (pinfunction "NC_17") (pintype "passive+no_connect"))
    )
    (net (code "66") (name "unconnected-(U2-NC-Pad18)") (class "Default")
      (node (ref "U2") (pin "18") (pinfunction "NC_18") (pintype "passive+no_connect"))
    )
    (net (code "67") (name "unconnected-(U2-NC-Pad19)") (class "Default")
      (node (ref "U2") (pin "19") (pinfunction "NC_19") (pintype "passive+no_connect"))
    )
    (net (code "68") (name "unconnected-(U2-NC-Pad20)") (class "Default")
      (node (ref "U2") (pin "20") (pinfunction "NC_20") (pintype "passive+no_connect"))
    )
    (net (code "69") (name "unconnected-(U2-NC-Pad21)") (class "Default")
      (node (ref "U2") (pin "21") (pinfunction "NC_21") (pintype "passive+no_connect"))
    )
    (net (code "70") (name "unconnected-(U2-NC-Pad22)") (class "Default")
      (node (ref "U2") (pin "22") (pinfunction "NC_22") (pintype "passive+no_connect"))
    )
    (net (code "71") (name "unconnected-(U2-NC-Pad32)") (class "Default")
      (node (ref "U2") (pin "32") (pinfunction "NC_32") (pintype "passive+no_connect"))
    )
    (net (code "72") (name "unconnected-(U2-SENSOR_VN(GPIO39,_ADC1_CH3,_RTC_GPIO3)-Pad5)") (class "Default")
      (node (ref "U2") (pin "5") (pinfunction "SENSOR_VN(GPIO39,_ADC1_CH3,_RTC_GPIO3)_5") (pintype "passive"))
    )
    (net (code "73") (name "unconnected-(U3-CTS#-Pad9)") (class "Default")
      (node (ref "U3") (pin "9") (pinfunction "CTS#_9") (pintype "passive+no_connect"))
    )
    (net (code "74") (name "unconnected-(U3-DCD#-Pad12)") (class "Default")
      (node (ref "U3") (pin "12") (pinfunction "DCD#_12") (pintype "passive+no_connect"))
    )
    (net (code "75") (name "unconnected-(U3-DSR#-Pad10)") (class "Default")
      (node (ref "U3") (pin "10") (pinfunction "DSR#_10") (pintype "passive+no_connect"))
    )
    (net (code "76") (name "unconnected-(U3-R232-Pad15)") (class "Default")
      (node (ref "U3") (pin "15") (pinfunction "R232_15") (pintype "passive+no_connect"))
    )
    (net (code "77") (name "unconnected-(U3-RI#-Pad11)") (class "Default")
      (node (ref "U3") (pin "11") (pinfunction "RI#_11") (pintype "passive+no_connect"))
    )
    (net (code "78") (name "unconnected-(U3-XI-Pad7)") (class "Default")
      (node (ref "U3") (pin "7") (pinfunction "XI_7") (pintype "passive+no_connect"))
    )
    (net (code "79") (name "unconnected-(U3-XO-Pad8)") (class "Default")
      (node (ref "U3") (pin "8") (pinfunction "XO_8") (pintype "passive+no_connect"))
    )
    (net (code "80") (name "unconnected-(U5-IN2+-Pad5)") (class "Default")
      (node (ref "U5") (pin "5") (pinfunction "IN2+_5") (pintype "passive+no_connect"))
    )
    (net (code "81") (name "unconnected-(U5-IN2--Pad6)") (class "Default")
      (node (ref "U5") (pin "6") (pinfunction "IN2-_6") (pintype "passive+no_connect"))
    )
    (net (code "82") (name "unconnected-(U5-OUT2-Pad7)") (class "Default")
      (node (ref "U5") (pin "7") (pinfunction "OUT2_7") (pintype "passive+no_connect"))
    )
    (net (code "83") (name "unconnected-(U6-ENA-Pad5)") (class "Default")
      (node (ref "U6") (pin "5") (pinfunction "ENA_5") (pintype "passive+no_connect"))
    )
    (net (code "84") (name "unconnected-(U6-NC-Pad2)") (class "Default")
      (node (ref "U6") (pin "2") (pinfunction "NC_2") (pintype "passive+no_connect"))
    )
    (net (code "85") (name "unconnected-(U6-NC-Pad3)") (class "Default")
      (node (ref "U6") (pin "3") (pinfunction "NC_3") (pintype "passive+no_connect"))
    )
  )
)
